# CLKB_SFP_wrapper.net
KiCad netlist of a schematic drawn in Altium Designer
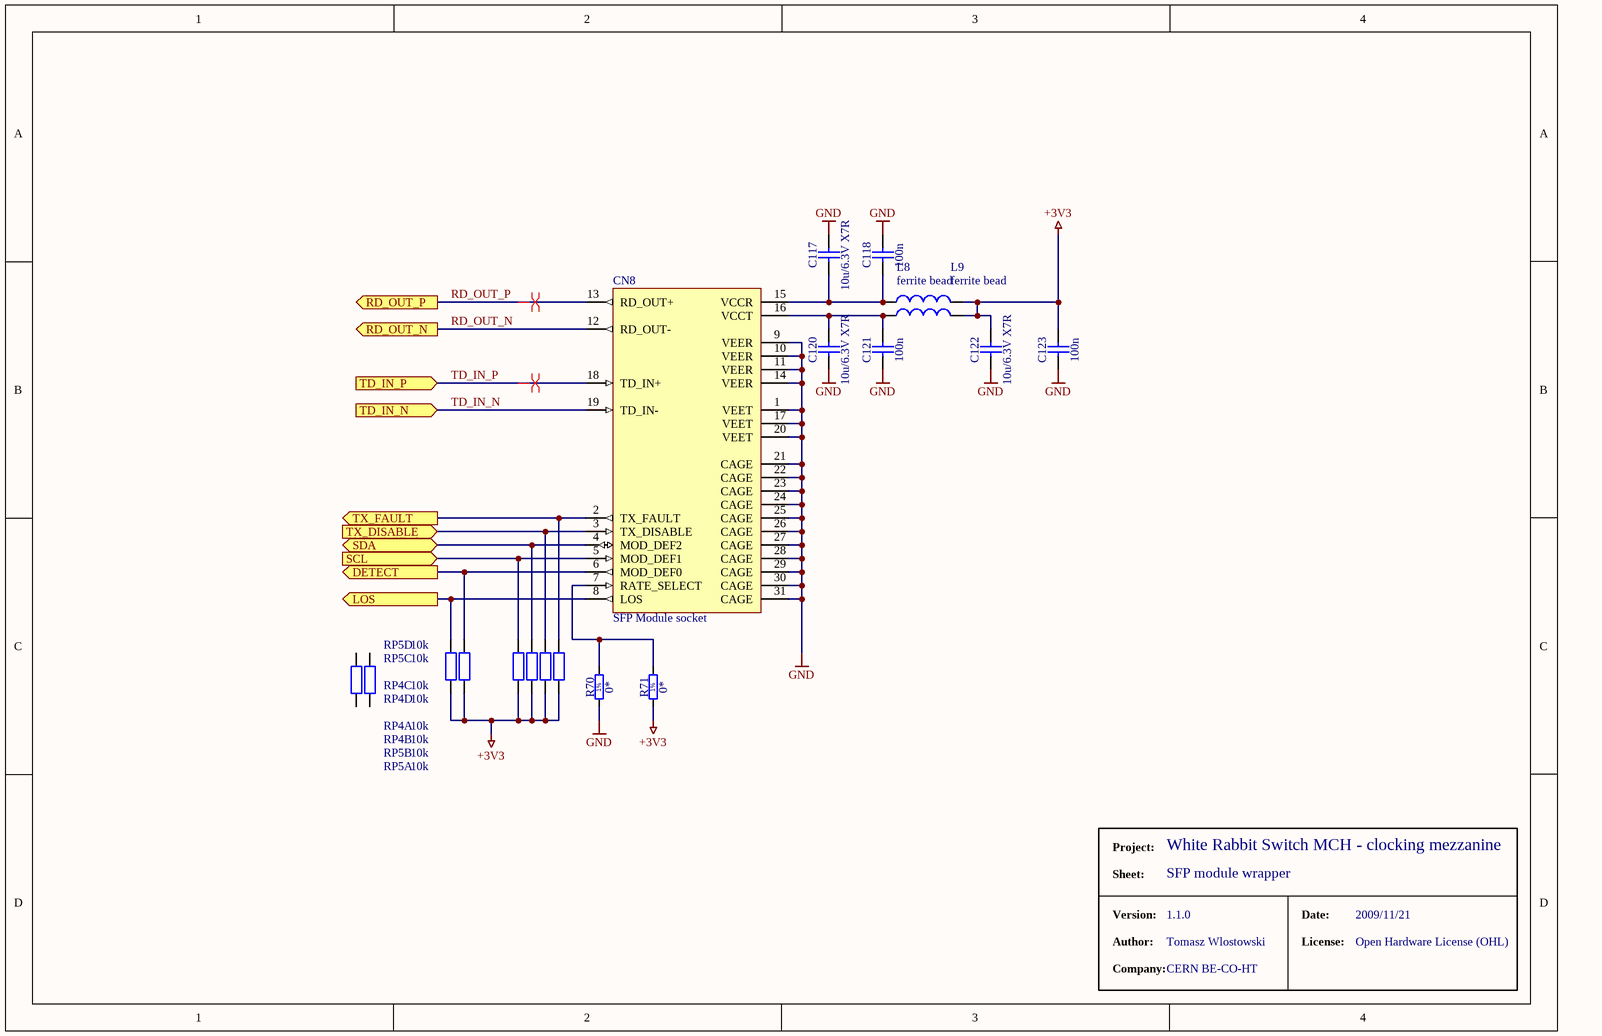
[diagram p0: CLKB_SFP_wrapper.SchDoc]

(export (version "E")
  (design (tool "Eeschema 10.0.6"))
  (components
    (comp (ref "C117")
      (value "10u/6.3V X7R")
      (footprint "CAPC3216X140N")
      (description "Non-polarised capacitor")
      (fields
        (field (name "PART NUMBER") "CC1206_10UF_10V_10%_X7R")
        (field (name "VOLTAGE") "10V")
        (field (name "AUTHOR") "CERN DEM JLC")
      )
      (libsource (lib "Capacitors") (part "Capacitor - non polarized"))
    )
    (comp (ref "C118")
      (value "100n")
      (footprint "CAPC1608X87N")
      (description "Non-polarised capacitor")
      (fields
        (field (name "PART NUMBER") "CC0603_100NF_50V_10%_X7R")
        (field (name "VOLTAGE") "50V")
        (field (name "AUTHOR") "CERN DEM JLC")
      )
      (libsource (lib "Capacitors") (part "Capacitor - non polarized"))
    )
    (comp (ref "C120")
      (value "10u/6.3V X7R")
      (footprint "CAPC3216X140N")
      (description "Non-polarised capacitor")
      (fields
        (field (name "PART NUMBER") "CC1206_10UF_10V_10%_X7R")
        (field (name "VOLTAGE") "10V")
        (field (name "AUTHOR") "CERN DEM JLC")
      )
      (libsource (lib "Capacitors") (part "Capacitor - non polarized"))
    )
    (comp (ref "C121")
      (value "100n")
      (footprint "CAPC1608X87N")
      (description "Non-polarised capacitor")
      (fields
        (field (name "PART NUMBER") "CC0603_100NF_50V_10%_X7R")
        (field (name "VOLTAGE") "50V")
        (field (name "AUTHOR") "CERN DEM JLC")
      )
      (libsource (lib "Capacitors") (part "Capacitor - non polarized"))
    )
    (comp (ref "C122")
      (value "10u/6.3V X7R")
      (footprint "CAPC3216X140N")
      (description "Non-polarised capacitor")
      (fields
        (field (name "PART NUMBER") "CC1206_10UF_10V_10%_X7R")
        (field (name "VOLTAGE") "10V")
        (field (name "AUTHOR") "CERN DEM JLC")
      )
      (libsource (lib "Capacitors") (part "Capacitor - non polarized"))
    )
    (comp (ref "C123")
      (value "100n")
      (footprint "CAPC1608X87N")
      (description "Non-polarised capacitor")
      (fields
        (field (name "PART NUMBER") "CC0603_100NF_50V_10%_X7R")
        (field (name "VOLTAGE") "50V")
        (field (name "AUTHOR") "CERN DEM JLC")
      )
      (libsource (lib "Capacitors") (part "Capacitor - non polarized"))
    )
    (comp (ref "CN8")
      (value "SFP Module socket")
      (footprint "SFP_SINGLE_PORT")
      (description "Socket for SFP module")
      (libsource (lib "wr_switch") (part "SFP_SOCKET_SINGLE"))
    )
    (comp (ref "L8")
      (value "ferrite bead")
      (footprint "INDC2012-0805")
      (description "Ferrite bead")
      (fields (field (name "Comment") "Inductor") (field (name "PUBLISHER") "Altium Limited"))
      (libsource (lib "Miscellaneous Devices") (part "Inductor"))
    )
    (comp (ref "L9")
      (value "ferrite bead")
      (footprint "INDC2012-0805")
      (description "Ferrite bead")
      (fields (field (name "Comment") "Inductor") (field (name "PUBLISHER") "Altium Limited"))
      (libsource (lib "Miscellaneous Devices") (part "Inductor"))
    )
    (comp (ref "R70")
      (value "0*")
      (footprint "RESC1608X55N")
      (description "Resistor - 1%")
      (fields
        (field (name "PART NUMBER") "R0603_0R_JUMPER")
        (field (name "MANUFACTURER") "GENERIC")
        (field (name "AUTHOR") "CERN DEM JLC")
      )
      (libsource (lib "Resistors") (part "Resistor - 1%"))
    )
    (comp (ref "R71")
      (value "0*")
      (footprint "RESC1608X55N")
      (description "Resistor - 1%")
      (fields
        (field (name "PART NUMBER") "R0603_0R_JUMPER")
        (field (name "MANUFACTURER") "GENERIC")
        (field (name "AUTHOR") "CERN DEM JLC")
      )
      (libsource (lib "Resistors") (part "Resistor - 1%"))
    )
    (comp (ref "RP4")
      (value "10k")
      (footprint "YC124")
      (description "4-resistor pack")
      (fields (field (name "Comment") "10k 0804"))
      (libsource (lib "wr_switch") (part "Res_Pack4_10k_YC124"))
    )
    (comp (ref "RP5")
      (value "10k")
      (footprint "YC124")
      (description "4-resistor pack")
      (fields (field (name "Comment") "10k 0804"))
      (libsource (lib "wr_switch") (part "Res_Pack4_10k_YC124"))
    )
  )
  (nets
    (net (code "1") (name "+3V3") (class "Default")
      (node (ref "C122") (pin "2") (pinfunction "2_2") (pintype "passive"))
      (node (ref "C123") (pin "2") (pinfunction "2_2") (pintype "passive"))
      (node (ref "L8") (pin "2") (pinfunction "2_2") (pintype "passive"))
      (node (ref "L9") (pin "2") (pinfunction "2_2") (pintype "passive"))
      (node (ref "R71") (pin "1") (pinfunction "1_1") (pintype "passive"))
      (node (ref "RP4") (pin "1") (pinfunction "A_1") (pintype "passive"))
      (node (ref "RP4") (pin "2") (pinfunction "A_2") (pintype "passive"))
      (node (ref "RP4") (pin "3") (pinfunction "A_3") (pintype "passive"))
      (node (ref "RP4") (pin "4") (pinfunction "A_4") (pintype "passive"))
      (node (ref "RP5") (pin "1") (pinfunction "A_1") (pintype "passive"))
      (node (ref "RP5") (pin "2") (pinfunction "A_2") (pintype "passive"))
    )
    (net (code "2") (name "/DETECT") (class "Default")
      (node (ref "CN8") (pin "6") (pinfunction "MOD_DEF0_6") (pintype "output"))
      (node (ref "RP4") (pin "6") (pinfunction "B_6") (pintype "passive"))
    )
    (net (code "3") (name "/LOS") (class "Default")
      (node (ref "CN8") (pin "8") (pinfunction "LOS_8") (pintype "output"))
      (node (ref "RP4") (pin "5") (pinfunction "B_5") (pintype "passive"))
    )
    (net (code "4") (name "/RD_OUT_N") (class "Default")
      (node (ref "CN8") (pin "12") (pinfunction "RD_OUT-_12") (pintype "output"))
    )
    (net (code "5") (name "/RD_OUT_P") (class "Default")
      (node (ref "CN8") (pin "13") (pinfunction "RD_OUT+_13") (pintype "output"))
    )
    (net (code "6") (name "/SCL") (class "Default")
      (node (ref "CN8") (pin "5") (pinfunction "MOD_DEF1_5") (pintype "input"))
      (node (ref "RP4") (pin "7") (pinfunction "B_7") (pintype "passive"))
    )
    (net (code "7") (name "/SDA") (class "Default")
      (node (ref "CN8") (pin "4") (pinfunction "MOD_DEF2_4") (pintype "bidirectional"))
      (node (ref "RP4") (pin "8") (pinfunction "B_8") (pintype "passive"))
    )
    (net (code "8") (name "/TD_IN_N") (class "Default")
      (node (ref "CN8") (pin "19") (pinfunction "TD_IN-_19") (pintype "input"))
    )
    (net (code "9") (name "/TD_IN_P") (class "Default")
      (node (ref "CN8") (pin "18") (pinfunction "TD_IN+_18") (pintype "input"))
    )
    (net (code "10") (name "/TX_DISABLE") (class "Default")
      (node (ref "CN8") (pin "3") (pinfunction "TX_DISABLE_3") (pintype "input"))
      (node (ref "RP5") (pin "7") (pinfunction "B_7") (pintype "passive"))
    )
    (net (code "11") (name "/TX_FAULT") (class "Default")
      (node (ref "CN8") (pin "2") (pinfunction "TX_FAULT_2") (pintype "output"))
      (node (ref "RP5") (pin "8") (pinfunction "B_8") (pintype "passive"))
    )
    (net (code "12") (name "GND") (class "Default")
      (node (ref "C117") (pin "2") (pinfunction "2_2") (pintype "passive"))
      (node (ref "C118") (pin "2") (pinfunction "2_2") (pintype "passive"))
      (node (ref "C120") (pin "1") (pinfunction "1_1") (pintype "passive"))
      (node (ref "C121") (pin "1") (pinfunction "1_1") (pintype "passive"))
      (node (ref "C122") (pin "1") (pinfunction "1_1") (pintype "passive"))
      (node (ref "C123") (pin "1") (pinfunction "1_1") (pintype "passive"))
      (node (ref "CN8") (pin "1") (pinfunction "VEET_1") (pintype "power_in"))
      (node (ref "CN8") (pin "10") (pinfunction "VEER_10") (pintype "power_in"))
      (node (ref "CN8") (pin "11") (pinfunction "VEER_11") (pintype "power_in"))
      (node (ref "CN8") (pin "14") (pinfunction "VEER_14") (pintype "power_in"))
      (node (ref "CN8") (pin "17") (pinfunction "VEET_17") (pintype "power_in"))
      (node (ref "CN8") (pin "20") (pinfunction "VEET_20") (pintype "power_in"))
      (node (ref "CN8") (pin "21") (pinfunction "CAGE_21") (pintype "power_in"))
      (node (ref "CN8") (pin "22") (pinfunction "CAGE_22") (pintype "power_in"))
      (node (ref "CN8") (pin "23") (pinfunction "CAGE_23") (pintype "power_in"))
      (node (ref "CN8") (pin "24") (pinfunction "CAGE_24") (pintype "power_in"))
      (node (ref "CN8") (pin "25") (pinfunction "CAGE_25") (pintype "power_in"))
      (node (ref "CN8") (pin "26") (pinfunction "CAGE_26") (pintype "power_in"))
      (node (ref "CN8") (pin "27") (pinfunction "CAGE_27") (pintype "power_in"))
      (node (ref "CN8") (pin "28") (pinfunction "CAGE_28") (pintype "power_in"))
      (node (ref "CN8") (pin "29") (pinfunction "CAGE_29") (pintype "power_in"))
      (node (ref "CN8") (pin "30") (pinfunction "CAGE_30") (pintype "power_in"))
      (node (ref "CN8") (pin "31") (pinfunction "CAGE_31") (pintype "power_in"))
      (node (ref "CN8") (pin "9") (pinfunction "VEER_9") (pintype "power_in"))
      (node (ref "R70") (pin "1") (pinfunction "1_1") (pintype "passive"))
    )
    (net (code "13") (name "Net-(CN8-RATE_SELECT)") (class "Default")
      (node (ref "CN8") (pin "7") (pinfunction "RATE_SELECT_7") (pintype "input"))
      (node (ref "R70") (pin "2") (pinfunction "2_2") (pintype "passive"))
      (node (ref "R71") (pin "2") (pinfunction "2_2") (pintype "passive"))
    )
    (net (code "14") (name "Net-(CN8-VCCR)") (class "Default")
      (node (ref "C117") (pin "1") (pinfunction "1_1") (pintype "passive"))
      (node (ref "C118") (pin "1") (pinfunction "1_1") (pintype "passive"))
      (node (ref "CN8") (pin "15") (pinfunction "VCCR_15") (pintype "power_in"))
      (node (ref "L9") (pin "1") (pinfunction "1_1") (pintype "passive"))
    )
    (net (code "15") (name "Net-(CN8-VCCT)") (class "Default")
      (node (ref "C120") (pin "2") (pinfunction "2_2") (pintype "passive"))
      (node (ref "C121") (pin "2") (pinfunction "2_2") (pintype "passive"))
      (node (ref "CN8") (pin "16") (pinfunction "VCCT_16") (pintype "power_in"))
      (node (ref "L8") (pin "1") (pinfunction "1_1") (pintype "passive"))
    )
    (net (code "16") (name "unconnected-(RP5C-A-Pad3)") (class "Default")
      (node (ref "RP5") (pin "3") (pinfunction "A_3") (pintype "passive"))
    )
    (net (code "17") (name "unconnected-(RP5C-B-Pad6)") (class "Default")
      (node (ref "RP5") (pin "6") (pinfunction "B_6") (pintype "passive"))
    )
    (net (code "18") (name "unconnected-(RP5D-A-Pad4)") (class "Default")
      (node (ref "RP5") (pin "4") (pinfunction "A_4") (pintype "passive"))
    )
    (net (code "19") (name "unconnected-(RP5D-B-Pad5)") (class "Default")
      (node (ref "RP5") (pin "5") (pinfunction "B_5") (pintype "passive"))
    )
  )
)
